# tube_timbre_trasher_1-9-22-fix.net
KiCad netlist of a schematic drawn in EAGLE
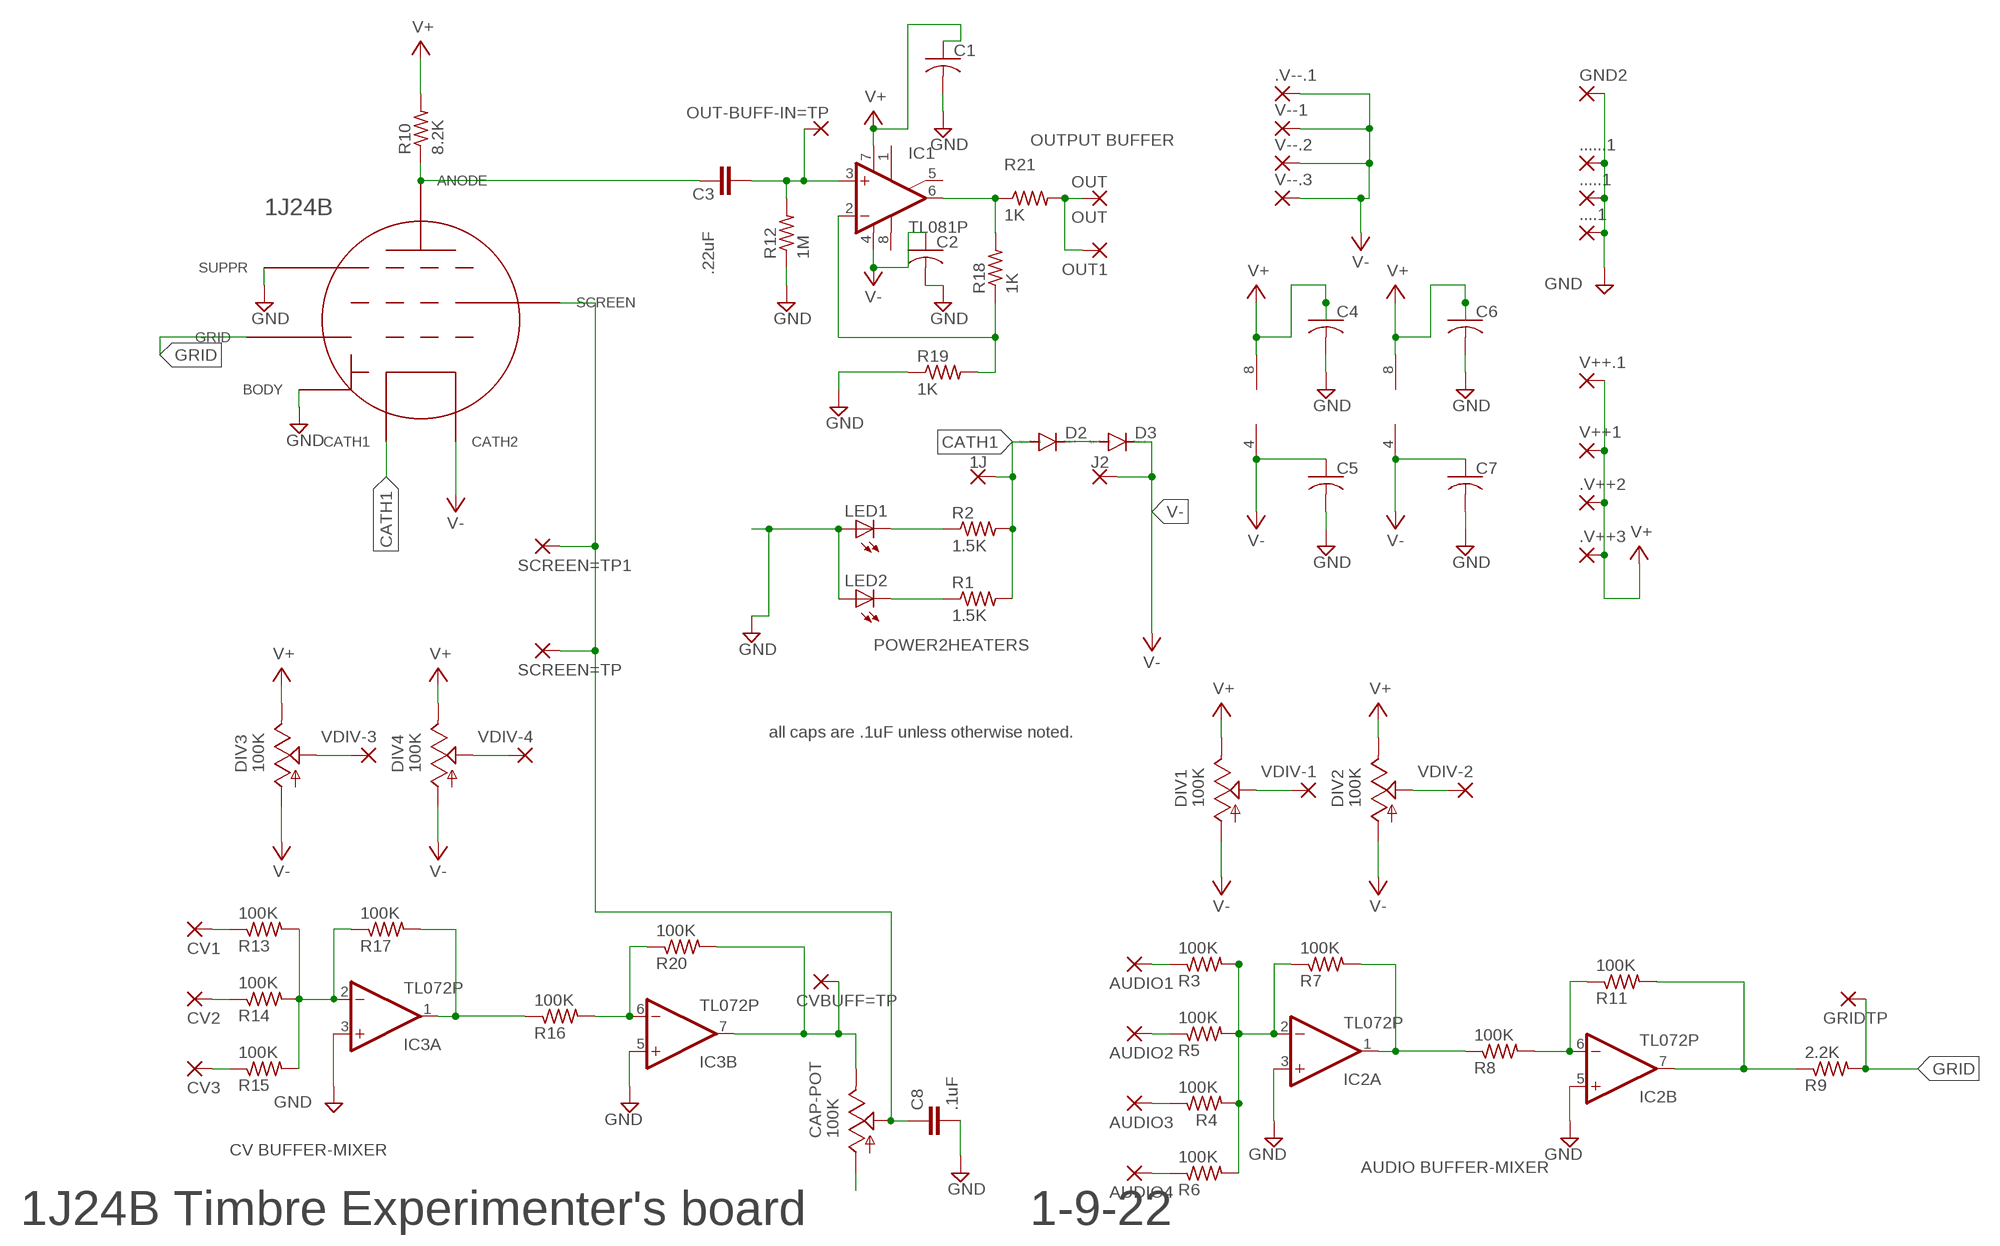
[diagram p0: schematic, sheet 1]

(export (version "E")
  (design (tool "Eeschema 10.0.6"))
  (components
    (comp (ref "......1")
      (value "3,17/1,3")
      (footprint "eagle-import:3,17_1,3")
      (libsource (lib "eagle-import") (part "wirepad_412_3,17/1,3"))
    )
    (comp (ref ".....1")
      (value "3,17/1,3")
      (footprint "eagle-import:3,17_1,3")
      (libsource (lib "eagle-import") (part "wirepad_412_3,17/1,3"))
    )
    (comp (ref "....1")
      (value "3,17/1,3")
      (footprint "eagle-import:3,17_1,3")
      (libsource (lib "eagle-import") (part "wirepad_412_3,17/1,3"))
    )
    (comp (ref ".V++2")
      (value "2,54/1,0")
      (footprint "eagle-import:2,54_1,0")
      (libsource (lib "eagle-import") (part "2,54/1,0"))
    )
    (comp (ref ".V++3")
      (value "2,54/1,0")
      (footprint "eagle-import:2,54_1,0")
      (libsource (lib "eagle-import") (part "2,54/1,0"))
    )
    (comp (ref ".V--.1")
      (value "3,17/1,3")
      (footprint "eagle-import:3,17_1,3")
      (libsource (lib "eagle-import") (part "3,17/1,3"))
    )
    (comp (ref "1J")
      (value "1")
      (footprint "eagle-import:1,6_0,9")
      (fields (field (name "SPICEPREFIX") "X"))
      (libsource (lib "eagle-import") (part "WIREPAD1,6/0,9"))
    )
    (comp (ref "1J24B")
      (value "1J24B")
      (footprint "eagle-import:6PINSOLDER")
      (fields (field (name "SPICEPREFIX") "X"))
      (libsource (lib "eagle-import") (part "1J24B"))
    )
    (comp (ref "AUDIO1")
      (value "3,17/1,3")
      (footprint "eagle-import:3,17_1,3")
      (fields (field (name "SPICEPREFIX") "X"))
      (libsource (lib "eagle-import") (part "wirepad_412_3,17/1,3"))
    )
    (comp (ref "AUDIO2")
      (value "3,17/1,3")
      (footprint "eagle-import:3,17_1,3")
      (fields (field (name "SPICEPREFIX") "X"))
      (libsource (lib "eagle-import") (part "wirepad_412_3,17/1,3"))
    )
    (comp (ref "AUDIO3")
      (value "3,17/1,3")
      (footprint "eagle-import:3,17_1,3")
      (fields (field (name "SPICEPREFIX") "X"))
      (libsource (lib "eagle-import") (part "wirepad_412_3,17/1,3"))
    )
    (comp (ref "AUDIO4")
      (value "3,17/1,3")
      (footprint "eagle-import:3,17_1,3")
      (fields (field (name "SPICEPREFIX") "X"))
      (libsource (lib "eagle-import") (part "wirepad_412_3,17/1,3"))
    )
    (comp (ref "C1")
      (value "C-US025-025X050")
      (footprint "eagle-import:C025-025X050")
      (libsource (lib "eagle-import") (part "C-US025-025X050"))
    )
    (comp (ref "C2")
      (value "C-US025-025X050")
      (footprint "eagle-import:C025-025X050")
      (libsource (lib "eagle-import") (part "C-US025-025X050"))
    )
    (comp (ref "C3")
      (value ".22uF")
      (footprint "eagle-import:C5B3.5")
      (fields (field (name "SPICEPREFIX") "C"))
      (libsource (lib "eagle-import") (part "capacitor-wima_116_C5/3.5"))
    )
    (comp (ref "C4")
      (value "C-US025-030X050")
      (footprint "eagle-import:C025-030X050")
      (fields (field (name "SPICEPREFIX") "C"))
      (libsource (lib "eagle-import") (part "C-US025-030X050"))
    )
    (comp (ref "C5")
      (value "C-US025-025X050")
      (footprint "eagle-import:C025-025X050")
      (fields (field (name "SPICEPREFIX") "C"))
      (libsource (lib "eagle-import") (part "C-US025-025X050"))
    )
    (comp (ref "C6")
      (value "C-US025-025X050")
      (footprint "eagle-import:C025-025X050")
      (fields (field (name "SPICEPREFIX") "C"))
      (libsource (lib "eagle-import") (part "C-US025-025X050"))
    )
    (comp (ref "C7")
      (value "C-US025-025X050")
      (footprint "eagle-import:C025-025X050")
      (fields (field (name "SPICEPREFIX") "C"))
      (libsource (lib "eagle-import") (part "C-US025-025X050"))
    )
    (comp (ref "C8")
      (value ".1uF")
      (footprint "eagle-import:C5B2.5")
      (fields (field (name "SPICEPREFIX") "C"))
      (libsource (lib "eagle-import") (part "C5/2.5"))
    )
    (comp (ref "CAP-POT")
      (value "100K")
      (footprint "eagle-import:9MM_SNAP-IN_POT")
      (fields (field (name "SPICEPREFIX") "J"))
      (libsource (lib "eagle-import") (part "9MM_SNAP-IN_POT_"))
    )
    (comp (ref "CV1")
      (value "3,17/1,3")
      (footprint "eagle-import:3,17_1,3")
      (fields (field (name "SPICEPREFIX") "X"))
      (libsource (lib "eagle-import") (part "wirepad_412_3,17/1,3"))
    )
    (comp (ref "CV2")
      (value "3,17/1,3")
      (footprint "eagle-import:3,17_1,3")
      (fields (field (name "SPICEPREFIX") "X"))
      (libsource (lib "eagle-import") (part "wirepad_412_3,17/1,3"))
    )
    (comp (ref "CV3")
      (value "3,17/1,3")
      (footprint "eagle-import:3,17_1,3")
      (fields (field (name "SPICEPREFIX") "X"))
      (libsource (lib "eagle-import") (part "wirepad_412_3,17/1,3"))
    )
    (comp (ref "CVBUFF=TP")
      (value "3,17/1,3")
      (footprint "eagle-import:3,17_1,3")
      (fields (field (name "SPICEPREFIX") "X"))
      (libsource (lib "eagle-import") (part "wirepad_412_3,17/1,3"))
    )
    (comp (ref "D2")
      (value "1N4148DO35-7")
      (footprint "eagle-import:DO35-7")
      (fields (field (name "SPICEPREFIX") "D"))
      (libsource (lib "eagle-import") (part "1N4148DO35-7"))
    )
    (comp (ref "D3")
      (value "1N4148DO35-7")
      (footprint "eagle-import:DO35-7")
      (fields (field (name "SPICEPREFIX") "D"))
      (libsource (lib "eagle-import") (part "1N4148DO35-7"))
    )
    (comp (ref "DIV1")
      (value "100K")
      (footprint "eagle-import:9MM_SNAP-IN_POT")
      (fields (field (name "SPICEPREFIX") "J"))
      (libsource (lib "eagle-import") (part "9MM_SNAP-IN_POT_"))
    )
    (comp (ref "DIV2")
      (value "100K")
      (footprint "eagle-import:9MM_SNAP-IN_POT")
      (fields (field (name "SPICEPREFIX") "J"))
      (libsource (lib "eagle-import") (part "9MM_SNAP-IN_POT_"))
    )
    (comp (ref "DIV3")
      (value "100K")
      (footprint "eagle-import:9MM_SNAP-IN_POT")
      (fields (field (name "SPICEPREFIX") "J"))
      (libsource (lib "eagle-import") (part "9MM_SNAP-IN_POT_"))
    )
    (comp (ref "DIV4")
      (value "100K")
      (footprint "eagle-import:9MM_SNAP-IN_POT")
      (fields (field (name "SPICEPREFIX") "J"))
      (libsource (lib "eagle-import") (part "9MM_SNAP-IN_POT_"))
    )
    (comp (ref "GND2")
      (value "3,17/1,3")
      (footprint "eagle-import:3,17_1,3")
      (libsource (lib "eagle-import") (part "wirepad_412_3,17/1,3"))
    )
    (comp (ref "GRIDTP")
      (value "3,17/1,3")
      (footprint "eagle-import:3,17_1,3")
      (fields (field (name "SPICEPREFIX") "X"))
      (libsource (lib "eagle-import") (part "wirepad_412_3,17/1,3"))
    )
    (comp (ref "IC1")
      (value "TL081P")
      (footprint "eagle-import:DIL08")
      (fields (field (name "SPICEPREFIX") "X"))
      (libsource (lib "eagle-import") (part "TL081P"))
    )
    (comp (ref "IC2")
      (value "TL072P")
      (footprint "eagle-import:DIL08")
      (fields (field (name "SPICEPREFIX") "B"))
      (libsource (lib "eagle-import") (part "TL072P"))
    )
    (comp (ref "IC3")
      (value "TL072P")
      (footprint "eagle-import:DIL08")
      (fields (field (name "SPICEPREFIX") "B"))
      (libsource (lib "eagle-import") (part "TL072P"))
    )
    (comp (ref "J2")
      (value "1")
      (footprint "eagle-import:1,6_0,9")
      (fields (field (name "SPICEPREFIX") "X"))
      (libsource (lib "eagle-import") (part "WIREPAD1,6/0,9"))
    )
    (comp (ref "LED1")
      (value "LED3MM")
      (footprint "eagle-import:LED3MM")
      (fields (field (name "SPICEPREFIX") "L"))
      (libsource (lib "eagle-import") (part "LED3MM"))
    )
    (comp (ref "LED2")
      (value "LED3MM")
      (footprint "eagle-import:LED3MM")
      (fields (field (name "SPICEPREFIX") "L"))
      (libsource (lib "eagle-import") (part "LED3MM"))
    )
    (comp (ref "OUT")
      (value "OUT")
      (footprint "eagle-import:3,17_1,3")
      (fields (field (name "SPICEPREFIX") "X"))
      (libsource (lib "eagle-import") (part "wirepad_412_3,17/1,3"))
    )
    (comp (ref "OUT-BUFF-IN=TP")
      (value "3,17/1,3")
      (footprint "eagle-import:3,17_1,3")
      (fields (field (name "SPICEPREFIX") "X"))
      (libsource (lib "eagle-import") (part "wirepad_412_3,17/1,3"))
    )
    (comp (ref "OUT1")
      (value "3,17/1,3")
      (footprint "eagle-import:3,17_1,3")
      (fields (field (name "SPICEPREFIX") "X"))
      (libsource (lib "eagle-import") (part "wirepad_412_3,17/1,3"))
    )
    (comp (ref "R1")
      (value "1.5K")
      (footprint "eagle-import:0207_10")
      (fields (field (name "SPICEPREFIX") "R"))
      (libsource (lib "eagle-import") (part "resistor_348_R-US_0207/10"))
    )
    (comp (ref "R2")
      (value "1.5K")
      (footprint "eagle-import:0207_10")
      (fields (field (name "SPICEPREFIX") "R"))
      (libsource (lib "eagle-import") (part "resistor_348_R-US_0207/10"))
    )
    (comp (ref "R3")
      (value "100K")
      (footprint "eagle-import:0204_7")
      (fields (field (name "SPICEPREFIX") "R"))
      (libsource (lib "eagle-import") (part "R-US_0204/7"))
    )
    (comp (ref "R4")
      (value "100K")
      (footprint "eagle-import:0204_7")
      (fields (field (name "SPICEPREFIX") "R"))
      (libsource (lib "eagle-import") (part "R-US_0204/7"))
    )
    (comp (ref "R5")
      (value "100K")
      (footprint "eagle-import:0204_7")
      (fields (field (name "SPICEPREFIX") "R"))
      (libsource (lib "eagle-import") (part "R-US_0204/7"))
    )
    (comp (ref "R6")
      (value "100K")
      (footprint "eagle-import:0204_7")
      (fields (field (name "SPICEPREFIX") "R"))
      (libsource (lib "eagle-import") (part "R-US_0204/7"))
    )
    (comp (ref "R7")
      (value "100K")
      (footprint "eagle-import:0204_7")
      (fields (field (name "SPICEPREFIX") "R"))
      (libsource (lib "eagle-import") (part "R-US_0204/7"))
    )
    (comp (ref "R8")
      (value "100K")
      (footprint "eagle-import:0204_7")
      (fields (field (name "SPICEPREFIX") "R"))
      (libsource (lib "eagle-import") (part "R-US_0204/7"))
    )
    (comp (ref "R9")
      (value "2.2K")
      (footprint "eagle-import:0204_7")
      (fields (field (name "SPICEPREFIX") "R"))
      (libsource (lib "eagle-import") (part "R-US_0204/7"))
    )
    (comp (ref "R10")
      (value "8.2K")
      (footprint "eagle-import:0207_15")
      (fields (field (name "SPICEPREFIX") "R"))
      (libsource (lib "eagle-import") (part "rcl_334_R-US_0207/15"))
    )
    (comp (ref "R11")
      (value "100K")
      (footprint "eagle-import:0204_7")
      (fields (field (name "SPICEPREFIX") "R"))
      (libsource (lib "eagle-import") (part "R-US_0204/7"))
    )
    (comp (ref "R12")
      (value "1M")
      (footprint "eagle-import:0204_7")
      (fields (field (name "SPICEPREFIX") "R"))
      (libsource (lib "eagle-import") (part "R-US_0204/7"))
    )
    (comp (ref "R13")
      (value "100K")
      (footprint "eagle-import:0204_7")
      (fields (field (name "SPICEPREFIX") "R"))
      (libsource (lib "eagle-import") (part "R-US_0204/7"))
    )
    (comp (ref "R14")
      (value "100K")
      (footprint "eagle-import:0204_7")
      (fields (field (name "SPICEPREFIX") "R"))
      (libsource (lib "eagle-import") (part "R-US_0204/7"))
    )
    (comp (ref "R15")
      (value "100K")
      (footprint "eagle-import:0204_7")
      (fields (field (name "SPICEPREFIX") "R"))
      (libsource (lib "eagle-import") (part "R-US_0204/7"))
    )
    (comp (ref "R16")
      (value "100K")
      (footprint "eagle-import:0204_7")
      (fields (field (name "SPICEPREFIX") "R"))
      (libsource (lib "eagle-import") (part "R-US_0204/7"))
    )
    (comp (ref "R17")
      (value "100K")
      (footprint "eagle-import:0204_7")
      (fields (field (name "SPICEPREFIX") "R"))
      (libsource (lib "eagle-import") (part "R-US_0204/7"))
    )
    (comp (ref "R18")
      (value "1K")
      (footprint "eagle-import:0204_7")
      (fields (field (name "SPICEPREFIX") "R"))
      (libsource (lib "eagle-import") (part "R-US_0204/7"))
    )
    (comp (ref "R19")
      (value "1K")
      (footprint "eagle-import:0204_7")
      (fields (field (name "SPICEPREFIX") "R"))
      (libsource (lib "eagle-import") (part "R-US_0204/7"))
    )
    (comp (ref "R20")
      (value "100K")
      (footprint "eagle-import:0204_7")
      (fields (field (name "SPICEPREFIX") "R"))
      (libsource (lib "eagle-import") (part "R-US_0204/7"))
    )
    (comp (ref "R21")
      (value "1K")
      (footprint "eagle-import:0204_7")
      (fields (field (name "SPICEPREFIX") "R"))
      (libsource (lib "eagle-import") (part "R-US_0204/7"))
    )
    (comp (ref "SCREEN=TP")
      (value "3,17/1,3")
      (footprint "eagle-import:3,17_1,3")
      (fields (field (name "SPICEPREFIX") "X"))
      (libsource (lib "eagle-import") (part "wirepad_412_3,17/1,3"))
    )
    (comp (ref "SCREEN=TP1")
      (value "3,17/1,3")
      (footprint "eagle-import:3,17_1,3")
      (fields (field (name "SPICEPREFIX") "X"))
      (libsource (lib "eagle-import") (part "wirepad_412_3,17/1,3"))
    )
    (comp (ref "V++.1")
      (value "2,54/1,0")
      (footprint "eagle-import:2,54_1,0")
      (libsource (lib "eagle-import") (part "2,54/1,0"))
    )
    (comp (ref "V++1")
      (value "2,54/1,0")
      (footprint "eagle-import:2,54_1,0")
      (libsource (lib "eagle-import") (part "2,54/1,0"))
    )
    (comp (ref "V--.2")
      (value "3,17/1,3")
      (footprint "eagle-import:3,17_1,3")
      (libsource (lib "eagle-import") (part "3,17/1,3"))
    )
    (comp (ref "V--.3")
      (value "3,17/1,3")
      (footprint "eagle-import:3,17_1,3")
      (libsource (lib "eagle-import") (part "3,17/1,3"))
    )
    (comp (ref "V--1")
      (value "3,17/1,3")
      (footprint "eagle-import:3,17_1,3")
      (libsource (lib "eagle-import") (part "3,17/1,3"))
    )
    (comp (ref "VDIV-1")
      (value "3,17/1,3")
      (footprint "eagle-import:3,17_1,3")
      (fields (field (name "SPICEPREFIX") "X"))
      (libsource (lib "eagle-import") (part "wirepad_412_3,17/1,3"))
    )
    (comp (ref "VDIV-2")
      (value "3,17/1,3")
      (footprint "eagle-import:3,17_1,3")
      (fields (field (name "SPICEPREFIX") "X"))
      (libsource (lib "eagle-import") (part "wirepad_412_3,17/1,3"))
    )
    (comp (ref "VDIV-3")
      (value "3,17/1,3")
      (footprint "eagle-import:3,17_1,3")
      (fields (field (name "SPICEPREFIX") "X"))
      (libsource (lib "eagle-import") (part "wirepad_412_3,17/1,3"))
    )
    (comp (ref "VDIV-4")
      (value "3,17/1,3")
      (footprint "eagle-import:3,17_1,3")
      (fields (field (name "SPICEPREFIX") "X"))
      (libsource (lib "eagle-import") (part "wirepad_412_3,17/1,3"))
    )
  )
  (nets
    (net (code "1") (name "CATH1") (class "Default")
      (node (ref "1J") (pin "1") (pinfunction "P_1") (pintype "passive"))
      (node (ref "1J24B") (pin "1-CATH") (pinfunction "CATH1_1-CATH") (pintype "bidirectional"))
      (node (ref "D2") (pin "A") (pinfunction "A_A") (pintype "passive"))
      (node (ref "R1") (pin "2") (pinfunction "2_2") (pintype "passive"))
      (node (ref "R2") (pin "2") (pinfunction "2_2") (pintype "passive"))
    )
    (net (code "2") (name "GND") (class "Default")
      (node (ref "......1") (pin "1") (pinfunction "P_1") (pintype "passive"))
      (node (ref ".....1") (pin "1") (pinfunction "P_1") (pintype "passive"))
      (node (ref "....1") (pin "1") (pinfunction "P_1") (pintype "passive"))
      (node (ref "1J24B") (pin "3-BDY") (pinfunction "BODY_3-BDY") (pintype "bidirectional"))
      (node (ref "1J24B") (pin "4-SUPP") (pinfunction "SUPPR_4-SUPP") (pintype "bidirectional"))
      (node (ref "C1") (pin "2") (pinfunction "2_2") (pintype "passive"))
      (node (ref "C2") (pin "2") (pinfunction "2_2") (pintype "passive"))
      (node (ref "C4") (pin "2") (pinfunction "2_2") (pintype "passive"))
      (node (ref "C5") (pin "2") (pinfunction "2_2") (pintype "passive"))
      (node (ref "C6") (pin "2") (pinfunction "2_2") (pintype "passive"))
      (node (ref "C7") (pin "2") (pinfunction "2_2") (pintype "passive"))
      (node (ref "C8") (pin "2") (pinfunction "2_2") (pintype "passive"))
      (node (ref "GND2") (pin "1") (pinfunction "P_1") (pintype "passive"))
      (node (ref "IC2") (pin "3") (pinfunction "+IN_3") (pintype "input"))
      (node (ref "IC2") (pin "5") (pinfunction "+IN_5") (pintype "input"))
      (node (ref "IC3") (pin "3") (pinfunction "+IN_3") (pintype "input"))
      (node (ref "IC3") (pin "5") (pinfunction "+IN_5") (pintype "input"))
      (node (ref "LED1") (pin "A") (pinfunction "A_A") (pintype "passive"))
      (node (ref "LED2") (pin "A") (pinfunction "A_A") (pintype "passive"))
      (node (ref "R12") (pin "1") (pinfunction "1_1") (pintype "passive"))
      (node (ref "R19") (pin "1") (pinfunction "1_1") (pintype "passive"))
    )
    (net (code "3") (name "GRID") (class "Default")
      (node (ref "1J24B") (pin "6-GRID") (pinfunction "GRID_6-GRID") (pintype "bidirectional"))
      (node (ref "GRIDTP") (pin "1") (pinfunction "P_1") (pintype "passive"))
      (node (ref "R9") (pin "2") (pinfunction "2_2") (pintype "passive"))
    )
    (net (code "4") (name "Net-(1J24B-ANODE)") (class "Default")
      (node (ref "1J24B") (pin "A") (pinfunction "ANODE_A") (pintype "bidirectional"))
      (node (ref "C3") (pin "1") (pinfunction "1_1") (pintype "passive"))
      (node (ref "R10") (pin "1") (pinfunction "1_1") (pintype "passive"))
    )
    (net (code "5") (name "Net-(1J24B-SCREEN)") (class "Default")
      (node (ref "1J24B") (pin "5-SCR") (pinfunction "SCREEN_5-SCR") (pintype "bidirectional"))
      (node (ref "C8") (pin "1") (pinfunction "1_1") (pintype "passive"))
      (node (ref "CAP-POT") (pin "2") (pinfunction "S_2") (pintype "passive"))
      (node (ref "SCREEN=TP") (pin "1") (pinfunction "P_1") (pintype "passive"))
      (node (ref "SCREEN=TP1") (pin "1") (pinfunction "P_1") (pintype "passive"))
    )
    (net (code "6") (name "Net-(AUDIO1-P)") (class "Default")
      (node (ref "AUDIO1") (pin "1") (pinfunction "P_1") (pintype "passive"))
      (node (ref "R3") (pin "1") (pinfunction "1_1") (pintype "passive"))
    )
    (net (code "7") (name "Net-(AUDIO2-P)") (class "Default")
      (node (ref "AUDIO2") (pin "1") (pinfunction "P_1") (pintype "passive"))
      (node (ref "R5") (pin "1") (pinfunction "1_1") (pintype "passive"))
    )
    (net (code "8") (name "Net-(AUDIO3-P)") (class "Default")
      (node (ref "AUDIO3") (pin "1") (pinfunction "P_1") (pintype "passive"))
      (node (ref "R4") (pin "1") (pinfunction "1_1") (pintype "passive"))
    )
    (net (code "9") (name "Net-(AUDIO4-P)") (class "Default")
      (node (ref "AUDIO4") (pin "1") (pinfunction "P_1") (pintype "passive"))
      (node (ref "R6") (pin "1") (pinfunction "1_1") (pintype "passive"))
    )
    (net (code "10") (name "Net-(CAP-POT-E)") (class "Default")
      (node (ref "CAP-POT") (pin "3") (pinfunction "E_3") (pintype "passive"))
      (node (ref "CVBUFF=TP") (pin "1") (pinfunction "P_1") (pintype "passive"))
      (node (ref "IC3") (pin "7") (pinfunction "OUT_7") (pintype "output"))
      (node (ref "R20") (pin "2") (pinfunction "2_2") (pintype "passive"))
    )
    (net (code "11") (name "Net-(CV1-P)") (class "Default")
      (node (ref "CV1") (pin "1") (pinfunction "P_1") (pintype "passive"))
      (node (ref "R13") (pin "1") (pinfunction "1_1") (pintype "passive"))
    )
    (net (code "12") (name "Net-(CV2-P)") (class "Default")
      (node (ref "CV2") (pin "1") (pinfunction "P_1") (pintype "passive"))
      (node (ref "R14") (pin "1") (pinfunction "1_1") (pintype "passive"))
    )
    (net (code "13") (name "Net-(CV3-P)") (class "Default")
      (node (ref "CV3") (pin "1") (pinfunction "P_1") (pintype "passive"))
      (node (ref "R15") (pin "1") (pinfunction "1_1") (pintype "passive"))
    )
    (net (code "14") (name "Net-(D2-PadC)") (class "Default")
      (node (ref "D2") (pin "C") (pinfunction "C_C") (pintype "passive"))
      (node (ref "D3") (pin "A") (pinfunction "A_A") (pintype "passive"))
    )
    (net (code "15") (name "Net-(DIV1-S)") (class "Default")
      (node (ref "DIV1") (pin "2") (pinfunction "S_2") (pintype "passive"))
      (node (ref "VDIV-1") (pin "1") (pinfunction "P_1") (pintype "passive"))
    )
    (net (code "16") (name "Net-(DIV2-S)") (class "Default")
      (node (ref "DIV2") (pin "2") (pinfunction "S_2") (pintype "passive"))
      (node (ref "VDIV-2") (pin "1") (pinfunction "P_1") (pintype "passive"))
    )
    (net (code "17") (name "Net-(DIV3-S)") (class "Default")
      (node (ref "DIV3") (pin "2") (pinfunction "S_2") (pintype "passive"))
      (node (ref "VDIV-3") (pin "1") (pinfunction "P_1") (pintype "passive"))
    )
    (net (code "18") (name "Net-(DIV4-S)") (class "Default")
      (node (ref "DIV4") (pin "2") (pinfunction "S_2") (pintype "passive"))
      (node (ref "VDIV-4") (pin "1") (pinfunction "P_1") (pintype "passive"))
    )
    (net (code "19") (name "Net-(IC1-+IN)") (class "Default")
      (node (ref "C3") (pin "2") (pinfunction "2_2") (pintype "passive"))
      (node (ref "IC1") (pin "3") (pinfunction "+IN_3") (pintype "input"))
      (node (ref "OUT-BUFF-IN=TP") (pin "1") (pinfunction "P_1") (pintype "passive"))
      (node (ref "R12") (pin "2") (pinfunction "2_2") (pintype "passive"))
    )
    (net (code "20") (name "Net-(IC1--IN)") (class "Default")
      (node (ref "IC1") (pin "2") (pinfunction "-IN_2") (pintype "input"))
      (node (ref "R18") (pin "1") (pinfunction "1_1") (pintype "passive"))
      (node (ref "R19") (pin "2") (pinfunction "2_2") (pintype "passive"))
    )
    (net (code "21") (name "Net-(IC1-OUT)") (class "Default")
      (node (ref "IC1") (pin "6") (pinfunction "OUT_6") (pintype "output"))
      (node (ref "R18") (pin "2") (pinfunction "2_2") (pintype "passive"))
      (node (ref "R21") (pin "1") (pinfunction "1_1") (pintype "passive"))
    )
    (net (code "22") (name "Net-(IC2A--IN)") (class "Default")
      (node (ref "IC2") (pin "2") (pinfunction "-IN_2") (pintype "input"))
      (node (ref "R3") (pin "2") (pinfunction "2_2") (pintype "passive"))
      (node (ref "R4") (pin "2") (pinfunction "2_2") (pintype "passive"))
      (node (ref "R5") (pin "2") (pinfunction "2_2") (pintype "passive"))
      (node (ref "R6") (pin "2") (pinfunction "2_2") (pintype "passive"))
      (node (ref "R7") (pin "1") (pinfunction "1_1") (pintype "passive"))
    )
    (net (code "23") (name "Net-(IC2A-OUT)") (class "Default")
      (node (ref "IC2") (pin "1") (pinfunction "OUT_1") (pintype "output"))
      (node (ref "R7") (pin "2") (pinfunction "2_2") (pintype "passive"))
      (node (ref "R8") (pin "1") (pinfunction "1_1") (pintype "passive"))
    )
    (net (code "24") (name "Net-(IC2B--IN)") (class "Default")
      (node (ref "IC2") (pin "6") (pinfunction "-IN_6") (pintype "input"))
      (node (ref "R11") (pin "1") (pinfunction "1_1") (pintype "passive"))
      (node (ref "R8") (pin "2") (pinfunction "2_2") (pintype "passive"))
    )
    (net (code "25") (name "Net-(IC2B-OUT)") (class "Default")
      (node (ref "IC2") (pin "7") (pinfunction "OUT_7") (pintype "output"))
      (node (ref "R11") (pin "2") (pinfunction "2_2") (pintype "passive"))
      (node (ref "R9") (pin "1") (pinfunction "1_1") (pintype "passive"))
    )
    (net (code "26") (name "Net-(IC3A--IN)") (class "Default")
      (node (ref "IC3") (pin "2") (pinfunction "-IN_2") (pintype "input"))
      (node (ref "R13") (pin "2") (pinfunction "2_2") (pintype "passive"))
      (node (ref "R14") (pin "2") (pinfunction "2_2") (pintype "passive"))
      (node (ref "R15") (pin "2") (pinfunction "2_2") (pintype "passive"))
      (node (ref "R17") (pin "1") (pinfunction "1_1") (pintype "passive"))
    )
    (net (code "27") (name "Net-(IC3A-OUT)") (class "Default")
      (node (ref "IC3") (pin "1") (pinfunction "OUT_1") (pintype "output"))
      (node (ref "R16") (pin "1") (pinfunction "1_1") (pintype "passive"))
      (node (ref "R17") (pin "2") (pinfunction "2_2") (pintype "passive"))
    )
    (net (code "28") (name "Net-(IC3B--IN)") (class "Default")
      (node (ref "IC3") (pin "6") (pinfunction "-IN_6") (pintype "input"))
      (node (ref "R16") (pin "2") (pinfunction "2_2") (pintype "passive"))
      (node (ref "R20") (pin "1") (pinfunction "1_1") (pintype "passive"))
    )
    (net (code "29") (name "Net-(LED1-C)") (class "Default")
      (node (ref "LED1") (pin "K") (pinfunction "C_K") (pintype "passive"))
      (node (ref "R2") (pin "1") (pinfunction "1_1") (pintype "passive"))
    )
    (net (code "30") (name "Net-(LED2-C)") (class "Default")
      (node (ref "LED2") (pin "K") (pinfunction "C_K") (pintype "passive"))
      (node (ref "R1") (pin "1") (pinfunction "1_1") (pintype "passive"))
    )
    (net (code "31") (name "Net-(OUT-P)") (class "Default")
      (node (ref "OUT") (pin "1") (pinfunction "P_1") (pintype "passive"))
      (node (ref "OUT1") (pin "1") (pinfunction "P_1") (pintype "passive"))
      (node (ref "R21") (pin "2") (pinfunction "2_2") (pintype "passive"))
    )
    (net (code "32") (name "V+") (class "Default")
      (node (ref ".V++2") (pin "1") (pinfunction "P_1") (pintype "passive"))
      (node (ref ".V++3") (pin "1") (pinfunction "P_1") (pintype "passive"))
      (node (ref "C1") (pin "1") (pinfunction "1_1") (pintype "passive"))
      (node (ref "C4") (pin "1") (pinfunction "1_1") (pintype "passive"))
      (node (ref "C6") (pin "1") (pinfunction "1_1") (pintype "passive"))
      (node (ref "DIV1") (pin "3") (pinfunction "E_3") (pintype "passive"))
      (node (ref "DIV2") (pin "3") (pinfunction "E_3") (pintype "passive"))
      (node (ref "DIV3") (pin "3") (pinfunction "E_3") (pintype "passive"))
      (node (ref "DIV4") (pin "3") (pinfunction "E_3") (pintype "passive"))
      (node (ref "IC1") (pin "7") (pinfunction "V+_7") (pintype "power_in"))
      (node (ref "IC2") (pin "8") (pinfunction "V+_8") (pintype "power_in"))
      (node (ref "IC3") (pin "8") (pinfunction "V+_8") (pintype "power_in"))
      (node (ref "R10") (pin "2") (pinfunction "2_2") (pintype "passive"))
      (node (ref "V++.1") (pin "1") (pinfunction "P_1") (pintype "passive"))
      (node (ref "V++1") (pin "1") (pinfunction "P_1") (pintype "passive"))
    )
    (net (code "33") (name "V-") (class "Default")
      (node (ref ".V--.1") (pin "1") (pinfunction "P_1") (pintype "passive"))
      (node (ref "1J24B") (pin "2-CATH") (pinfunction "CATH2_2-CATH") (pintype "bidirectional"))
      (node (ref "C2") (pin "1") (pinfunction "1_1") (pintype "passive"))
      (node (ref "C5") (pin "1") (pinfunction "1_1") (pintype "passive"))
      (node (ref "C7") (pin "1") (pinfunction "1_1") (pintype "passive"))
      (node (ref "D3") (pin "C") (pinfunction "C_C") (pintype "passive"))
      (node (ref "DIV1") (pin "1") (pinfunction "A_1") (pintype "passive"))
      (node (ref "DIV2") (pin "1") (pinfunction "A_1") (pintype "passive"))
      (node (ref "DIV3") (pin "1") (pinfunction "A_1") (pintype "passive"))
      (node (ref "DIV4") (pin "1") (pinfunction "A_1") (pintype "passive"))
      (node (ref "IC1") (pin "4") (pinfunction "V-_4") (pintype "power_in"))
      (node (ref "IC2") (pin "4") (pinfunction "V-_4") (pintype "power_in"))
      (node (ref "IC3") (pin "4") (pinfunction "V-_4") (pintype "power_in"))
      (node (ref "J2") (pin "1") (pinfunction "P_1") (pintype "passive"))
      (node (ref "V--.2") (pin "1") (pinfunction "P_1") (pintype "passive"))
      (node (ref "V--.3") (pin "1") (pinfunction "P_1") (pintype "passive"))
      (node (ref "V--1") (pin "1") (pinfunction "P_1") (pintype "passive"))
    )
    (net (code "34") (name "unconnected-(CAP-POT-A-Pad1)") (class "Default")
      (node (ref "CAP-POT") (pin "1") (pinfunction "A_1") (pintype "passive"))
    )
    (net (code "35") (name "unconnected-(IC1-ON1-Pad1)") (class "Default")
      (node (ref "IC1") (pin "1") (pinfunction "ON1_1") (pintype "passive"))
    )
    (net (code "36") (name "unconnected-(IC1-ON2-Pad5)") (class "Default")
      (node (ref "IC1") (pin "5") (pinfunction "ON2_5") (pintype "passive"))
    )
    (net (code "37") (name "unconnected-(IC1-OPT-Pad8)") (class "Default")
      (node (ref "IC1") (pin "8") (pinfunction "OPT_8") (pintype "passive"))
    )
  )
)
